# 03_ZIGBEE.net
KiCad netlist of a schematic drawn in Altium Designer
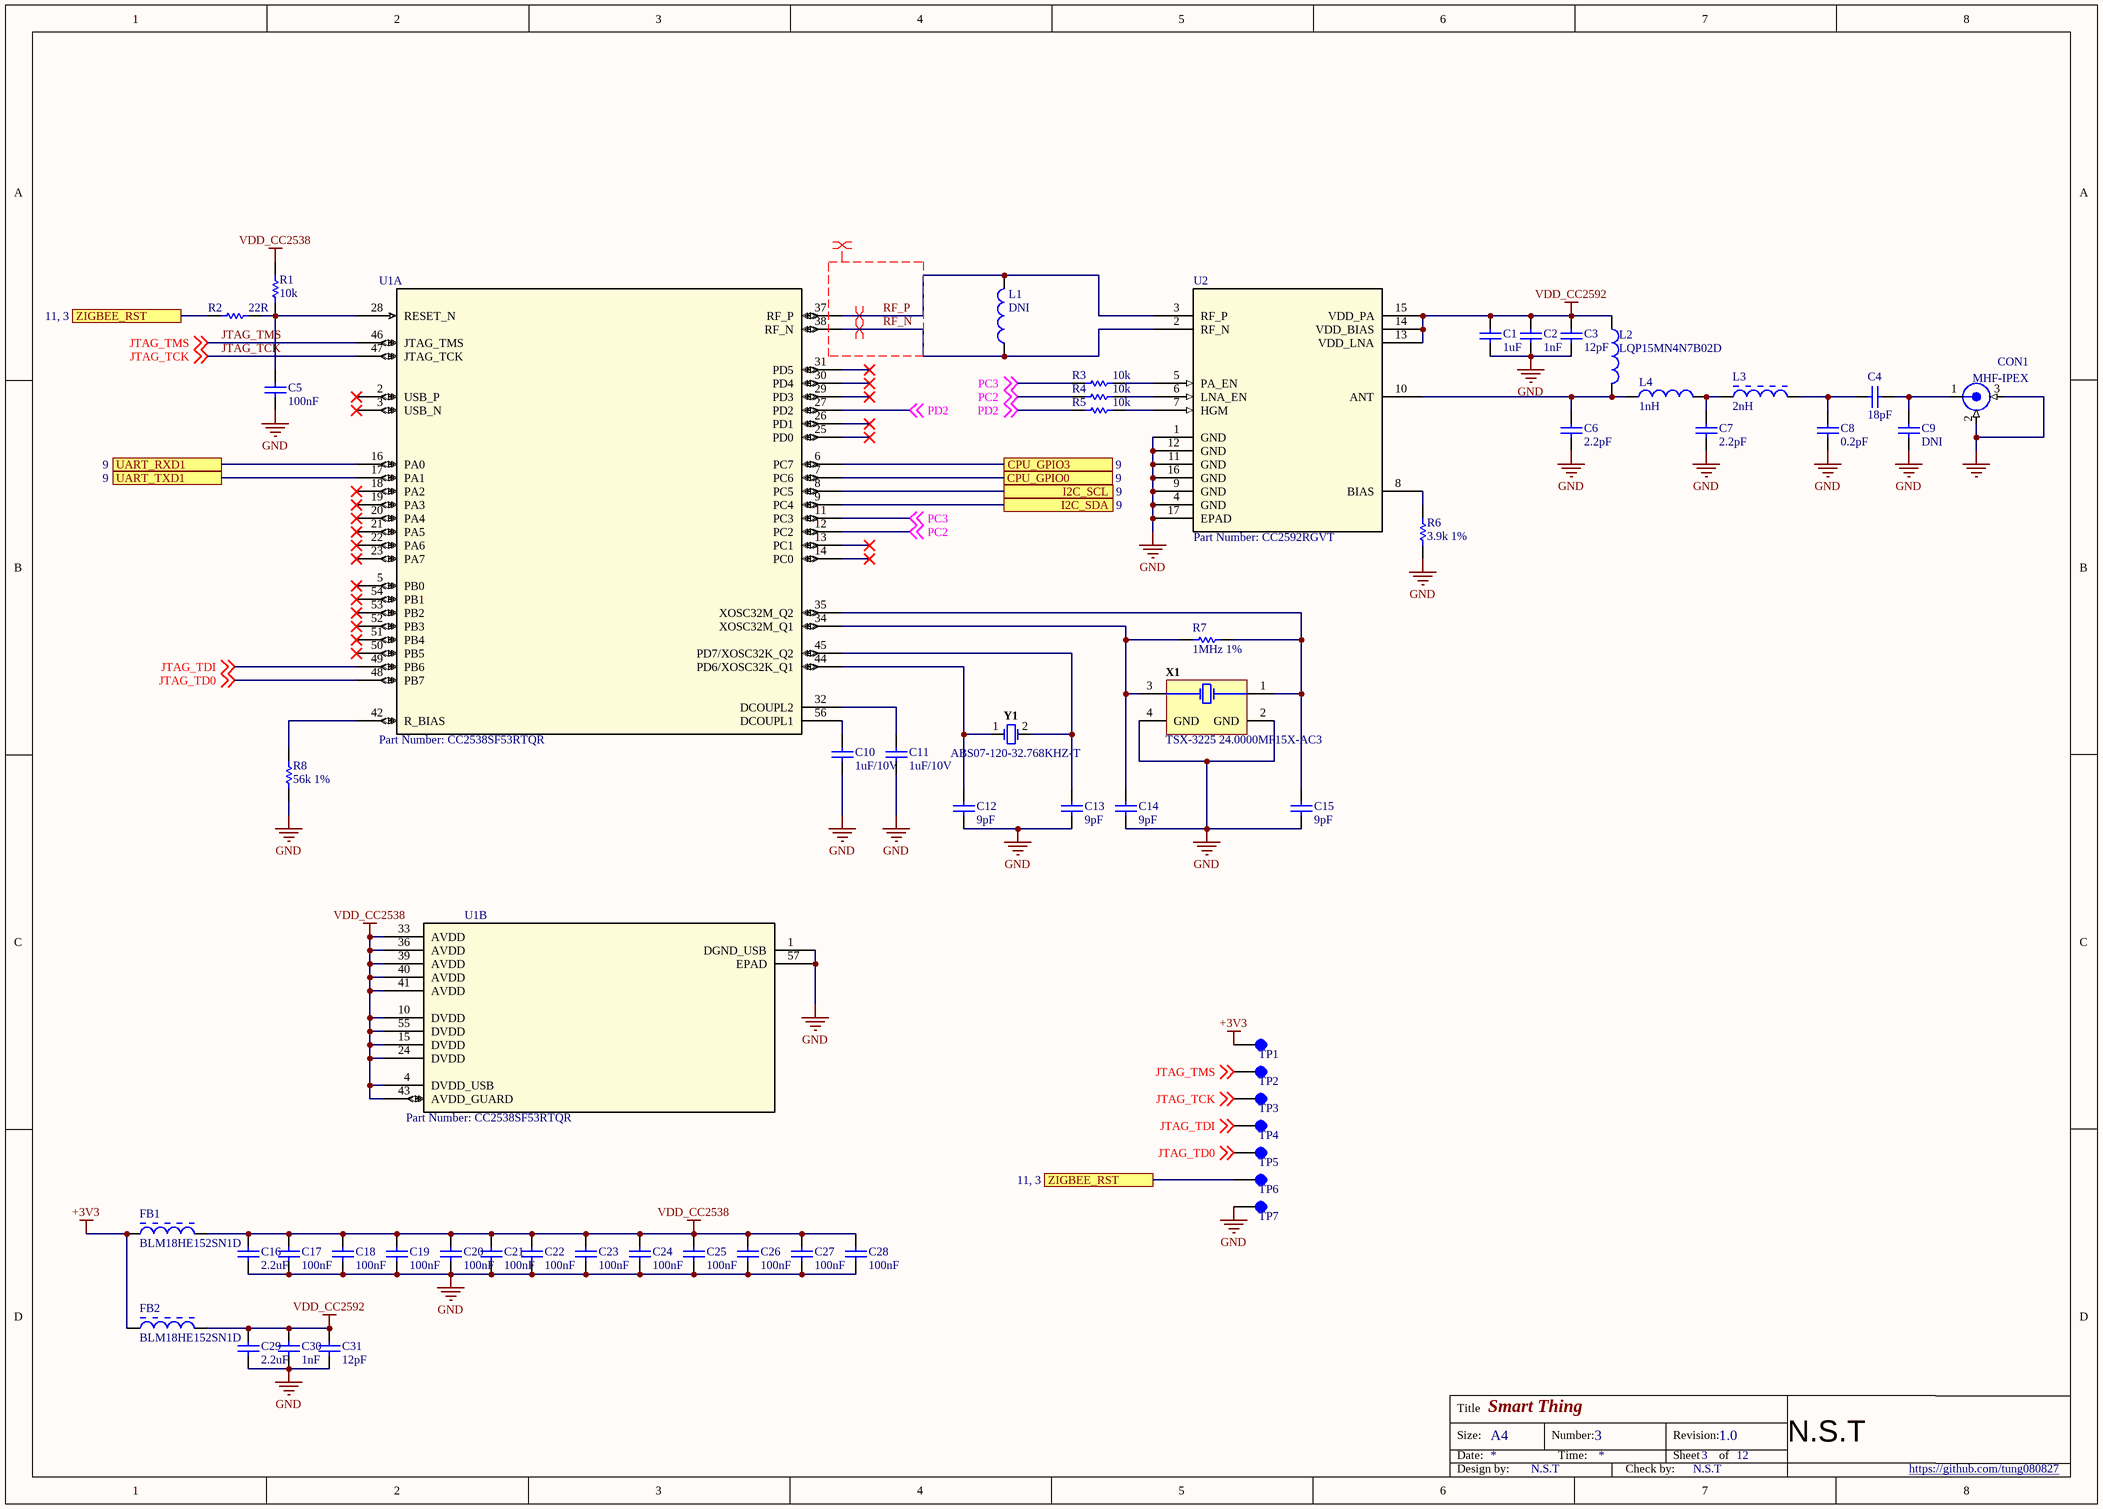
[diagram p0: 03. ZIGBEE.SchDoc]

(export (version "E")
  (design (tool "Eeschema 10.0.6"))
  (components
    (comp (ref "C1")
      (value "1uF")
      (footprint "CAPC1608X90X20NL10")
      (description "Chip Capacitor, 1 uF, +/- 10%, 50 V, -55 to 85 degC, 0603 (1608 Metric), RoHS, Tape and Reel")
      (fields
        (field (name "MANUFACTURER") "TDK")
        (field (name "PCN PART NUMBER") "MLCCPartNumberChange30/Nov/2012")
      )
      (libsource (lib "Altium Content Vault") (part "CAP-NP-2"))
    )
    (comp (ref "C2")
      (value "1nF")
      (footprint "CAPC1005X55X25NL05T10")
      (fields (field (name "PART NUMBER") "GRM1555C1H102JA01D") (field (name "MANUFACTURER") "Murata"))
      (libsource (lib "Altium Content Vault") (part "CAP"))
    )
    (comp (ref "C3")
      (value "12pF")
      (footprint "CAPC1005X55X25NL05T10")
      (fields (field (name "PART NUMBER") "GRM1555C1H120GA01D") (field (name "MANUFACTURER") "Murata"))
      (libsource (lib "Altium Content Vault") (part "CAP"))
    )
    (comp (ref "C4")
      (value "18pF")
      (footprint "CAPC1005X55X25NL05T10")
      (fields (field (name "PART NUMBER") "GJM1555C1H180GB01D") (field (name "MANUFACTURER") "Murata"))
      (libsource (lib "Altium Content Vault") (part "CAP"))
    )
    (comp (ref "C5")
      (value "100nF")
      (footprint "CAPC1005X56X25NL10T15")
      (fields
        (field (name "MANUFACTURER") "AVX Interconnect / Elco")
        (field (name "PART NUMBER") "04026D104KAT2A")
      )
      (libsource (lib "Altium Content Vault") (part "CAP"))
    )
    (comp (ref "C6")
      (value "2.2pF")
      (footprint "CAPC1005X55X25NL05T10")
      (fields (field (name "PART NUMBER") "GJM1555C1H2R2BB01D") (field (name "MANUFACTURER") "Murata"))
      (libsource (lib "Altium Content Vault") (part "CAP"))
    )
    (comp (ref "C7")
      (value "2.2pF")
      (footprint "CAPC1005X55X25NL05T10")
      (fields (field (name "PART NUMBER") "GJM1555C1H2R2BB01D") (field (name "MANUFACTURER") "Murata"))
      (libsource (lib "Altium Content Vault") (part "CAP"))
    )
    (comp (ref "C8")
      (value "0.2pF")
      (footprint "CAPC1005X55X25NL05T10")
      (fields (field (name "PART NUMBER") "GRM1555C1HR20WA01D") (field (name "MANUFACTURER") "Murata"))
      (libsource (lib "Altium Content Vault") (part "CAP"))
    )
    (comp (ref "C9")
      (value "DNI")
      (footprint "CAPC1005X55X25NL05T10")
      (fields (field (name "PART NUMBER") "GJM1555C1H180GB01D") (field (name "MANUFACTURER") "Murata"))
      (libsource (lib "Altium Content Vault") (part "CAP"))
    )
    (comp (ref "C10")
      (value "1uF/10V")
      (footprint "CAPC1005X55X25NL05T10")
      (fields (field (name "PART NUMBER") "GRM155R61A105KE15D") (field (name "MANUFACTURER") "Murata"))
      (libsource (lib "Altium Content Vault") (part "CAP"))
    )
    (comp (ref "C11")
      (value "1uF/10V")
      (footprint "CAPC1005X55X25NL05T10")
      (fields (field (name "PART NUMBER") "GRM155R61A105KE15D") (field (name "MANUFACTURER") "Murata"))
      (libsource (lib "Altium Content Vault") (part "CAP"))
    )
    (comp (ref "C12")
      (value "9pF")
      (footprint "CAPC1005X55X25NL05T10")
      (fields (field (name "PART NUMBER") "GJM1555C1H9R0CB01D") (field (name "MANUFACTURER") "Murata"))
      (libsource (lib "Altium Content Vault") (part "CAP"))
    )
    (comp (ref "C13")
      (value "9pF")
      (footprint "CAPC1005X55X25NL05T10")
      (fields (field (name "PART NUMBER") "GJM1555C1H9R0CB01D") (field (name "MANUFACTURER") "Murata"))
      (libsource (lib "Altium Content Vault") (part "CAP"))
    )
    (comp (ref "C14")
      (value "9pF")
      (footprint "CAPC1005X55X25NL05T10")
      (fields (field (name "PART NUMBER") "GJM1555C1H9R0CB01D") (field (name "MANUFACTURER") "Murata"))
      (libsource (lib "Altium Content Vault") (part "CAP"))
    )
    (comp (ref "C15")
      (value "9pF")
      (footprint "CAPC1005X55X25NL05T10")
      (fields (field (name "PART NUMBER") "GJM1555C1H9R0CB01D") (field (name "MANUFACTURER") "Murata"))
      (libsource (lib "Altium Content Vault") (part "CAP"))
    )
    (comp (ref "C16")
      (value "2.2uF")
      (footprint "CAPC1608X90X35NL10T15")
      (fields (field (name "MANUFACTURER") "Murata") (field (name "PART NUMBER") "GCM188R70J225KE22D"))
      (libsource (lib "Altium Content Vault") (part "CAP"))
    )
    (comp (ref "C17")
      (value "100nF")
      (footprint "CAPC1005X56X25NL10T15")
      (fields
        (field (name "MANUFACTURER") "AVX Interconnect / Elco")
        (field (name "PART NUMBER") "04026D104KAT2A")
      )
      (libsource (lib "Altium Content Vault") (part "CAP"))
    )
    (comp (ref "C18")
      (value "100nF")
      (footprint "CAPC1005X56X25NL10T15")
      (fields
        (field (name "MANUFACTURER") "AVX Interconnect / Elco")
        (field (name "PART NUMBER") "04026D104KAT2A")
      )
      (libsource (lib "Altium Content Vault") (part "CAP"))
    )
    (comp (ref "C19")
      (value "100nF")
      (footprint "CAPC1005X56X25NL10T15")
      (fields
        (field (name "MANUFACTURER") "AVX Interconnect / Elco")
        (field (name "PART NUMBER") "04026D104KAT2A")
      )
      (libsource (lib "Altium Content Vault") (part "CAP"))
    )
    (comp (ref "C20")
      (value "100nF")
      (footprint "CAPC1005X56X25NL10T15")
      (fields
        (field (name "MANUFACTURER") "AVX Interconnect / Elco")
        (field (name "PART NUMBER") "04026D104KAT2A")
      )
      (libsource (lib "Altium Content Vault") (part "CAP"))
    )
    (comp (ref "C21")
      (value "100nF")
      (footprint "CAPC1005X56X25NL10T15")
      (fields
        (field (name "MANUFACTURER") "AVX Interconnect / Elco")
        (field (name "PART NUMBER") "04026D104KAT2A")
      )
      (libsource (lib "Altium Content Vault") (part "CAP"))
    )
    (comp (ref "C22")
      (value "100nF")
      (footprint "CAPC1005X56X25NL10T15")
      (fields
        (field (name "MANUFACTURER") "AVX Interconnect / Elco")
        (field (name "PART NUMBER") "04026D104KAT2A")
      )
      (libsource (lib "Altium Content Vault") (part "CAP"))
    )
    (comp (ref "C23")
      (value "100nF")
      (footprint "CAPC1005X56X25NL10T15")
      (fields
        (field (name "MANUFACTURER") "AVX Interconnect / Elco")
        (field (name "PART NUMBER") "04026D104KAT2A")
      )
      (libsource (lib "Altium Content Vault") (part "CAP"))
    )
    (comp (ref "C24")
      (value "100nF")
      (footprint "CAPC1005X56X25NL10T15")
      (fields
        (field (name "MANUFACTURER") "AVX Interconnect / Elco")
        (field (name "PART NUMBER") "04026D104KAT2A")
      )
      (libsource (lib "Altium Content Vault") (part "CAP"))
    )
    (comp (ref "C25")
      (value "100nF")
      (footprint "CAPC1005X56X25NL10T15")
      (fields
        (field (name "MANUFACTURER") "AVX Interconnect / Elco")
        (field (name "PART NUMBER") "04026D104KAT2A")
      )
      (libsource (lib "Altium Content Vault") (part "CAP"))
    )
    (comp (ref "C26")
      (value "100nF")
      (footprint "CAPC1005X56X25NL10T15")
      (fields
        (field (name "MANUFACTURER") "AVX Interconnect / Elco")
        (field (name "PART NUMBER") "04026D104KAT2A")
      )
      (libsource (lib "Altium Content Vault") (part "CAP"))
    )
    (comp (ref "C27")
      (value "100nF")
      (footprint "CAPC1005X56X25NL10T15")
      (fields
        (field (name "MANUFACTURER") "AVX Interconnect / Elco")
        (field (name "PART NUMBER") "04026D104KAT2A")
      )
      (libsource (lib "Altium Content Vault") (part "CAP"))
    )
    (comp (ref "C28")
      (value "100nF")
      (footprint "CAPC1005X56X25NL10T15")
      (fields
        (field (name "MANUFACTURER") "AVX Interconnect / Elco")
        (field (name "PART NUMBER") "04026D104KAT2A")
      )
      (libsource (lib "Altium Content Vault") (part "CAP"))
    )
    (comp (ref "C29")
      (value "2.2uF")
      (footprint "CAPC1608X90X35NL10T15")
      (fields (field (name "MANUFACTURER") "Murata") (field (name "PART NUMBER") "GCM188R70J225KE22D"))
      (libsource (lib "Altium Content Vault") (part "CAP"))
    )
    (comp (ref "C30")
      (value "1nF")
      (footprint "CAPC1005X55X25NL05T10")
      (fields (field (name "PART NUMBER") "GRM1555C1H102JA01D") (field (name "MANUFACTURER") "Murata"))
      (libsource (lib "Altium Content Vault") (part "CAP"))
    )
    (comp (ref "C31")
      (value "12pF")
      (footprint "CAPC1005X55X25NL05T10")
      (fields (field (name "PART NUMBER") "GRM1555C1H120GA01D") (field (name "MANUFACTURER") "Murata"))
      (libsource (lib "Altium Content Vault") (part "CAP"))
    )
    (comp (ref "CON1")
      (value "MHF-IPEX")
      (footprint "I-PEX CON")
      (libsource (lib "MT7688AN") (part "SMA/UFLR"))
    )
    (comp (ref "FB1")
      (value "BLM18HE152SN1D")
      (footprint "MURA-BLM18-RF-H4-CHIP-2_V")
      (fields (field (name "MANUFACTURER") "Murata"))
      (libsource (lib "Altium Content Vault") (part "MURA-FB-2"))
    )
    (comp (ref "FB2")
      (value "BLM18HE152SN1D")
      (footprint "MURA-BLM18-RF-H4-CHIP-2_V")
      (fields (field (name "MANUFACTURER") "Murata"))
      (libsource (lib "Altium Content Vault") (part "MURA-FB-2"))
    )
    (comp (ref "L1")
      (value "DNI")
      (footprint "INDC1005X45X25NL10T10")
      (description "Chip Inductor, 1.8 nH, +/- 0.1 nH, 280 mA, -40 to 85 degC, 0402 (1005 Metric), RoHS, Tape and Reel")
      (fields (field (name "MANUFACTURER") "Murata"))
      (libsource (lib "Altium Content Vault") (part "IND-2"))
    )
    (comp (ref "L2")
      (value "LQP15MN4N7B02D")
      (footprint "INDC1005X45X25LL10T10")
      (description "Chip Inductor, 4.7 nH, +/- 0.1 nH, 160 mA, -40 to 85 degC, 0402 (1005 Metric), RoHS, Tape and Reel")
      (fields (field (name "MANUFACTURER") "Murata") (field (name "TOLERANCE") "0.1nH"))
      (libsource (lib "Altium Content Vault") (part "IND-2"))
    )
    (comp (ref "L3")
      (value "2nH")
      (footprint "MURA-IND0402_V")
      (fields (field (name "MANUFACTURER") "Murata") (field (name "PARTNUMBER") "LQG15HS2N0S02D"))
      (libsource (lib "Altium Content Vault") (part "MURA-INDC-2"))
    )
    (comp (ref "L4")
      (value "1nH")
      (footprint "INDC1005X45X25NL10T10")
      (description "Chip Inductor, 1 nH, +/- 0.1 nH, 400 mA, -40 to 85 degC, 0402 (1005 Metric), RoHS, Tape and Reel")
      (fields (field (name "PARTNUMBER") "LQP15MN1N0B02D"))
      (libsource (lib "Altium Content Vault") (part "IND-2"))
    )
    (comp (ref "R1")
      (value "10k")
      (footprint "RESC1005X40X25NL05T05")
      (fields (field (name "MANUFACTURER") "Vishay Dale") (field (name "PART NUMBER") "CRCW040210K0FKED"))
      (libsource (lib "Altium Content Vault") (part "RES"))
    )
    (comp (ref "R2")
      (value "22R")
      (footprint "RESC1005X40X25LL05T05")
      (description "Chip Resistor, 22 Ohm, +/- 1%, 0.1 W, -55 to 155 degC, 0402 (1005 Metric), RoHS, Tape and Reel")
      (fields (field (name "PARTNUMBER") "ERJ-2RKF22R0X") (field (name "TOLERANCE") "1%"))
      (libsource (lib "AM3358_DEV_BOARD") (part "RES-2"))
    )
    (comp (ref "R3")
      (value "10k")
      (footprint "RESC1005X40X25NL05T05")
      (fields (field (name "MANUFACTURER") "Vishay Dale") (field (name "PART NUMBER") "CRCW040210K0FKED"))
      (libsource (lib "Altium Content Vault") (part "RES"))
    )
    (comp (ref "R4")
      (value "10k")
      (footprint "RESC1005X40X25NL05T05")
      (fields (field (name "MANUFACTURER") "Vishay Dale") (field (name "PART NUMBER") "CRCW040210K0FKED"))
      (libsource (lib "Altium Content Vault") (part "RES"))
    )
    (comp (ref "R5")
      (value "10k")
      (footprint "RESC1005X40X25NL05T05")
      (fields (field (name "MANUFACTURER") "Vishay Dale") (field (name "PART NUMBER") "CRCW040210K0FKED"))
      (libsource (lib "Altium Content Vault") (part "RES"))
    )
    (comp (ref "R6")
      (value "3.9k 1%")
      (footprint "RESC1005X40X25NL05T05")
      (fields (field (name "MANUFACTURER") "Vishay Dale") (field (name "PART NUMBER") "CRCW04023K90FKED"))
      (libsource (lib "Altium Content Vault") (part "RES"))
    )
    (comp (ref "R7")
      (value "1MHz 1%")
      (footprint "RESC1005X40X25NL05T05")
      (fields (field (name "PART NUMBER") "CRCW04020000Z0ED") (field (name "MANUFACTURER") "Vishay Dale"))
      (libsource (lib "Altium Content Vault") (part "RES"))
    )
    (comp (ref "R8")
      (value "56k 1%")
      (footprint "RESC1005X40X25NL05T05")
      (fields (field (name "PART NUMBER") "CRCW040256K0FKED") (field (name "MANUFACTURER") "Vishay Dale"))
      (libsource (lib "Altium Content Vault") (part "RES"))
    )
    (comp (ref "TP1") (value "Test Point") (footprint "TP") (libsource (lib "SyTungNguyen") (part "TP")))
    (comp (ref "TP2") (value "Test Point") (footprint "TP") (libsource (lib "SyTungNguyen") (part "TP")))
    (comp (ref "TP3") (value "Test Point") (footprint "TP") (libsource (lib "SyTungNguyen") (part "TP")))
    (comp (ref "TP4") (value "Test Point") (footprint "TP") (libsource (lib "SyTungNguyen") (part "TP")))
    (comp (ref "TP5") (value "Test Point") (footprint "TP") (libsource (lib "SyTungNguyen") (part "TP")))
    (comp (ref "TP6") (value "Test Point") (footprint "TP") (libsource (lib "SyTungNguyen") (part "TP")))
    (comp (ref "TP7") (value "Test Point") (footprint "TP") (libsource (lib "SyTungNguyen") (part "TP")))
    (comp (ref "U1")
      (value "Part Number: CC2538SF53RTQR")
      (footprint "QFN56_6P7X6P7")
      (description "IC RF TxRx + MCU 802.15.4 6LoWPAN, Zigbee® 2.4GHz 56-VFQFN Exposed Pad")
      (fields
        (field (name "MANUFACTURER_PART_NUMBER") "CC2538SF53RTQR")
        (field (name "COPYRIGHT") "Copyright (C) 2018 Accelerated Designs. All rights reserved")
      )
      (libsource (lib "SyTungNguyen") (part "CC2538SF53RTQR"))
    )
    (comp (ref "U2")
      (value "Part Number: CC2592RGVT")
      (footprint "QFN16_2P16X2P16")
      (description "No Description Available")
      (fields
        (field (name "MANUFACTURER_PART_NUMBER") "CC2592RGVT")
        (field (name "COPYRIGHT") "Copyright (C) 2018 Accelerated Designs. All rights reserved")
      )
      (libsource (lib "SyTungNguyen") (part "CC2592RGVT"))
    )
    (comp (ref "X1")
      (value "TSX-3225 24.0000MF15X-AC3")
      (footprint "FP-NX3225SA-MFG")
      (description "MHz Range Crystal, 24 MHz, -40 to 85 degC, 4-Pin SMD, RoHS, Tape and Reel")
      (fields (field (name "TOLERANCE") "10PPM") (field (name "MANUFACTURER") "Epson"))
      (libsource (lib "AM3358_DEV_BOARD") (part "XTAL-1-3-4"))
    )
    (comp (ref "Y1")
      (value "ABS07-120-32.768KHZ-T")
      (footprint "ABRA-ABS07_A_V")
      (description "Tuning Fork Crystal, 32.768 KHz, +/- 20 ppm, -40 to 85 degC, 2-Pin SMD, RoHS, Tape and Reel")
      (fields (field (name "MANUFACTURER") "Abracon") (field (name "TOLERANCE") "20ppm"))
      (libsource (lib "Altium Content Vault") (part "XTAL-1-2-2"))
    )
  )
  (nets
    (net (code "1") (name "+3V3") (class "Default")
      (node (ref "FB1") (pin "1") (pinfunction "1_1") (pintype "passive"))
      (node (ref "FB2") (pin "1") (pinfunction "1_1") (pintype "passive"))
      (node (ref "TP1") (pin "1") (pintype "passive"))
    )
    (net (code "2") (name "/CPU_GPIO0") (class "Default")
      (node (ref "U1") (pin "7") (pinfunction "PC6_7") (pintype "bidirectional"))
    )
    (net (code "3") (name "/CPU_GPIO3") (class "Default")
      (node (ref "U1") (pin "6") (pinfunction "PC7_6") (pintype "bidirectional"))
    )
    (net (code "4") (name "/I2C_SCL") (class "Default")
      (node (ref "U1") (pin "8") (pinfunction "PC5_8") (pintype "bidirectional"))
    )
    (net (code "5") (name "/I2C_SDA") (class "Default")
      (node (ref "U1") (pin "9") (pinfunction "PC4_9") (pintype "bidirectional"))
    )
    (net (code "6") (name "/RF_N") (class "Default")
      (node (ref "L1") (pin "1") (pinfunction "1_1") (pintype "passive"))
      (node (ref "U1") (pin "38") (pinfunction "RF_N_38") (pintype "bidirectional"))
      (node (ref "U2") (pin "2") (pinfunction "RF_N_2") (pintype "passive"))
    )
    (net (code "7") (name "/RF_P") (class "Default")
      (node (ref "L1") (pin "2") (pinfunction "2_2") (pintype "passive"))
      (node (ref "U1") (pin "37") (pinfunction "RF_P_37") (pintype "bidirectional"))
      (node (ref "U2") (pin "3") (pinfunction "RF_P_3") (pintype "passive"))
    )
    (net (code "8") (name "/UART_RXD1") (class "Default")
      (node (ref "U1") (pin "16") (pinfunction "PA0_16") (pintype "bidirectional"))
    )
    (net (code "9") (name "/UART_TXD1") (class "Default")
      (node (ref "U1") (pin "17") (pinfunction "PA1_17") (pintype "bidirectional"))
    )
    (net (code "10") (name "/ZIGBEE_RST") (class "Default")
      (node (ref "R2") (pin "1") (pinfunction "1_1") (pintype "passive"))
      (node (ref "TP6") (pin "1") (pintype "passive"))
    )
    (net (code "11") (name "GND") (class "Default")
      (node (ref "C1") (pin "1") (pinfunction "1_1") (pintype "passive"))
      (node (ref "C10") (pin "1") (pinfunction "1_1") (pintype "passive"))
      (node (ref "C11") (pin "1") (pinfunction "1_1") (pintype "passive"))
      (node (ref "C12") (pin "1") (pinfunction "1_1") (pintype "passive"))
      (node (ref "C13") (pin "1") (pinfunction "1_1") (pintype "passive"))
      (node (ref "C14") (pin "1") (pinfunction "1_1") (pintype "passive"))
      (node (ref "C15") (pin "1") (pinfunction "1_1") (pintype "passive"))
      (node (ref "C16") (pin "1") (pinfunction "1_1") (pintype "passive"))
      (node (ref "C17") (pin "1") (pinfunction "1_1") (pintype "passive"))
      (node (ref "C18") (pin "1") (pinfunction "1_1") (pintype "passive"))
      (node (ref "C19") (pin "1") (pinfunction "1_1") (pintype "passive"))
      (node (ref "C2") (pin "1") (pinfunction "1_1") (pintype "passive"))
      (node (ref "C20") (pin "1") (pinfunction "1_1") (pintype "passive"))
      (node (ref "C21") (pin "1") (pinfunction "1_1") (pintype "passive"))
      (node (ref "C22") (pin "1") (pinfunction "1_1") (pintype "passive"))
      (node (ref "C23") (pin "1") (pinfunction "1_1") (pintype "passive"))
      (node (ref "C24") (pin "1") (pinfunction "1_1") (pintype "passive"))
      (node (ref "C25") (pin "1") (pinfunction "1_1") (pintype "passive"))
      (node (ref "C26") (pin "1") (pinfunction "1_1") (pintype "passive"))
      (node (ref "C27") (pin "1") (pinfunction "1_1") (pintype "passive"))
      (node (ref "C28") (pin "1") (pinfunction "1_1") (pintype "passive"))
      (node (ref "C29") (pin "1") (pinfunction "1_1") (pintype "passive"))
      (node (ref "C3") (pin "1") (pinfunction "1_1") (pintype "passive"))
      (node (ref "C30") (pin "1") (pinfunction "1_1") (pintype "passive"))
      (node (ref "C31") (pin "1") (pinfunction "1_1") (pintype "passive"))
      (node (ref "C5") (pin "1") (pinfunction "1_1") (pintype "passive"))
      (node (ref "C6") (pin "1") (pinfunction "1_1") (pintype "passive"))
      (node (ref "C7") (pin "1") (pinfunction "1_1") (pintype "passive"))
      (node (ref "C8") (pin "1") (pinfunction "1_1") (pintype "passive"))
      (node (ref "C9") (pin "1") (pinfunction "1_1") (pintype "passive"))
      (node (ref "CON1") (pin "2") (pinfunction "2_2") (pintype "input"))
      (node (ref "CON1") (pin "3") (pinfunction "GNDA_3") (pintype "input"))
      (node (ref "R6") (pin "1") (pinfunction "1_1") (pintype "passive"))
      (node (ref "R8") (pin "1") (pinfunction "1_1") (pintype "passive"))
      (node (ref "TP7") (pin "1") (pintype "passive"))
      (node (ref "U1") (pin "1") (pinfunction "DGND_USB_1") (pintype "power_in"))
      (node (ref "U1") (pin "57") (pinfunction "EPAD_57") (pintype "passive"))
      (node (ref "U2") (pin "1") (pinfunction "GND_1") (pintype "power_in"))
      (node (ref "U2") (pin "11") (pinfunction "GND_11") (pintype "power_in"))
      (node (ref "U2") (pin "12") (pinfunction "GND_12") (pintype "power_in"))
      (node (ref "U2") (pin "16") (pinfunction "GND_16") (pintype "power_in"))
      (node (ref "U2") (pin "17") (pinfunction "EPAD_17") (pintype "passive"))
      (node (ref "U2") (pin "4") (pinfunction "GND_4") (pintype "power_in"))
      (node (ref "U2") (pin "9") (pinfunction "GND_9") (pintype "power_in"))
      (node (ref "X1") (pin "2") (pinfunction "GND_2") (pintype "power_in"))
      (node (ref "X1") (pin "4") (pinfunction "GND_4") (pintype "power_in"))
    )
    (net (code "12") (name "JTAG_TCK") (class "Default")
      (node (ref "TP3") (pin "1") (pintype "passive"))
      (node (ref "U1") (pin "47") (pinfunction "JTAG_TCK_47") (pintype "bidirectional"))
    )
    (net (code "13") (name "JTAG_TD0") (class "Default")
      (node (ref "TP5") (pin "1") (pintype "passive"))
      (node (ref "U1") (pin "48") (pinfunction "PB7_48") (pintype "bidirectional"))
    )
    (net (code "14") (name "JTAG_TDI") (class "Default")
      (node (ref "TP4") (pin "1") (pintype "passive"))
      (node (ref "U1") (pin "49") (pinfunction "PB6_49") (pintype "bidirectional"))
    )
    (net (code "15") (name "JTAG_TMS") (class "Default")
      (node (ref "TP2") (pin "1") (pintype "passive"))
      (node (ref "U1") (pin "46") (pinfunction "JTAG_TMS_46") (pintype "bidirectional"))
    )
    (net (code "16") (name "Net-(C4-Pad1)") (class "Default")
      (node (ref "C4") (pin "1") (pinfunction "1_1") (pintype "passive"))
      (node (ref "C8") (pin "2") (pinfunction "2_2") (pintype "passive"))
      (node (ref "L3") (pin "2") (pinfunction "2_2") (pintype "passive"))
    )
    (net (code "17") (name "Net-(C4-Pad2)") (class "Default")
      (node (ref "C4") (pin "2") (pinfunction "2_2") (pintype "passive"))
      (node (ref "C9") (pin "2") (pinfunction "2_2") (pintype "passive"))
      (node (ref "CON1") (pin "1") (pinfunction "1_1") (pintype "passive"))
    )
    (net (code "18") (name "Net-(C7-Pad2)") (class "Default")
      (node (ref "C7") (pin "2") (pinfunction "2_2") (pintype "passive"))
      (node (ref "L3") (pin "1") (pinfunction "1_1") (pintype "passive"))
      (node (ref "L4") (pin "2") (pinfunction "2_2") (pintype "passive"))
    )
    (net (code "19") (name "Net-(U1A-DCOUPL1)") (class "Default")
      (node (ref "C10") (pin "2") (pinfunction "2_2") (pintype "passive"))
      (node (ref "U1") (pin "56") (pinfunction "DCOUPL1_56") (pintype "power_in"))
    )
    (net (code "20") (name "Net-(U1A-DCOUPL2)") (class "Default")
      (node (ref "C11") (pin "2") (pinfunction "2_2") (pintype "passive"))
      (node (ref "U1") (pin "32") (pinfunction "DCOUPL2_32") (pintype "power_in"))
    )
    (net (code "21") (name "Net-(U1A-PD6{slash}XOSC32K_Q1)") (class "Default")
      (node (ref "C12") (pin "2") (pinfunction "2_2") (pintype "passive"))
      (node (ref "U1") (pin "44") (pinfunction "PD6/XOSC32K_Q1_44") (pintype "bidirectional"))
      (node (ref "Y1") (pin "1") (pinfunction "1_1") (pintype "passive"))
    )
    (net (code "22") (name "Net-(U1A-PD7{slash}XOSC32K_Q2)") (class "Default")
      (node (ref "C13") (pin "2") (pinfunction "2_2") (pintype "passive"))
      (node (ref "U1") (pin "45") (pinfunction "PD7/XOSC32K_Q2_45") (pintype "bidirectional"))
      (node (ref "Y1") (pin "2") (pinfunction "2_2") (pintype "passive"))
    )
    (net (code "23") (name "Net-(U1A-RESET_N)") (class "Default")
      (node (ref "C5") (pin "2") (pinfunction "2_2") (pintype "passive"))
      (node (ref "R1") (pin "1") (pinfunction "1_1") (pintype "passive"))
      (node (ref "R2") (pin "2") (pinfunction "2_2") (pintype "passive"))
      (node (ref "U1") (pin "28") (pinfunction "RESET_N_28") (pintype "input"))
    )
    (net (code "24") (name "Net-(U1A-R_BIAS)") (class "Default")
      (node (ref "R8") (pin "2") (pinfunction "2_2") (pintype "passive"))
      (node (ref "U1") (pin "42") (pinfunction "R_BIAS_42") (pintype "bidirectional"))
    )
    (net (code "25") (name "Net-(U1A-XOSC32M_Q1)") (class "Default")
      (node (ref "C14") (pin "2") (pinfunction "2_2") (pintype "passive"))
      (node (ref "R7") (pin "1") (pinfunction "1_1") (pintype "passive"))
      (node (ref "U1") (pin "34") (pinfunction "XOSC32M_Q1_34") (pintype "bidirectional"))
      (node (ref "X1") (pin "3") (pinfunction "X2_3") (pintype "passive"))
    )
    (net (code "26") (name "Net-(U1A-XOSC32M_Q2)") (class "Default")
      (node (ref "C15") (pin "2") (pinfunction "2_2") (pintype "passive"))
      (node (ref "R7") (pin "2") (pinfunction "2_2") (pintype "passive"))
      (node (ref "U1") (pin "35") (pinfunction "XOSC32M_Q2_35") (pintype "bidirectional"))
      (node (ref "X1") (pin "1") (pinfunction "X1_1") (pintype "passive"))
    )
    (net (code "27") (name "Net-(U2-ANT)") (class "Default")
      (node (ref "C6") (pin "2") (pinfunction "2_2") (pintype "passive"))
      (node (ref "L2") (pin "2") (pinfunction "2_2") (pintype "passive"))
      (node (ref "L4") (pin "1") (pinfunction "1_1") (pintype "passive"))
      (node (ref "U2") (pin "10") (pinfunction "ANT_10") (pintype "passive"))
    )
    (net (code "28") (name "Net-(U2-BIAS)") (class "Default")
      (node (ref "R6") (pin "2") (pinfunction "2_2") (pintype "passive"))
      (node (ref "U2") (pin "8") (pinfunction "BIAS_8") (pintype "passive"))
    )
    (net (code "29") (name "Net-(U2-HGM)") (class "Default")
      (node (ref "R5") (pin "2") (pinfunction "2_2") (pintype "passive"))
      (node (ref "U2") (pin "7") (pinfunction "HGM_7") (pintype "input"))
    )
    (net (code "30") (name "Net-(U2-LNA_EN)") (class "Default")
      (node (ref "R4") (pin "2") (pinfunction "2_2") (pintype "passive"))
      (node (ref "U2") (pin "6") (pinfunction "LNA_EN_6") (pintype "input"))
    )
    (net (code "31") (name "Net-(U2-PA_EN)") (class "Default")
      (node (ref "R3") (pin "2") (pinfunction "2_2") (pintype "passive"))
      (node (ref "U2") (pin "5") (pinfunction "PA_EN_5") (pintype "input"))
    )
    (net (code "32") (name "PC2") (class "Default")
      (node (ref "R4") (pin "1") (pinfunction "1_1") (pintype "passive"))
      (node (ref "U1") (pin "12") (pinfunction "PC2_12") (pintype "bidirectional"))
    )
    (net (code "33") (name "PC3") (class "Default")
      (node (ref "R3") (pin "1") (pinfunction "1_1") (pintype "passive"))
      (node (ref "U1") (pin "11") (pinfunction "PC3_11") (pintype "bidirectional"))
    )
    (net (code "34") (name "PD2") (class "Default")
      (node (ref "R5") (pin "1") (pinfunction "1_1") (pintype "passive"))
      (node (ref "U1") (pin "27") (pinfunction "PD2_27") (pintype "bidirectional"))
    )
    (net (code "35") (name "VDD_CC2538") (class "Default")
      (node (ref "C16") (pin "2") (pinfunction "2_2") (pintype "passive"))
      (node (ref "C17") (pin "2") (pinfunction "2_2") (pintype "passive"))
      (node (ref "C18") (pin "2") (pinfunction "2_2") (pintype "passive"))
      (node (ref "C19") (pin "2") (pinfunction "2_2") (pintype "passive"))
      (node (ref "C20") (pin "2") (pinfunction "2_2") (pintype "passive"))
      (node (ref "C21") (pin "2") (pinfunction "2_2") (pintype "passive"))
      (node (ref "C22") (pin "2") (pinfunction "2_2") (pintype "passive"))
      (node (ref "C23") (pin "2") (pinfunction "2_2") (pintype "passive"))
      (node (ref "C24") (pin "2") (pinfunction "2_2") (pintype "passive"))
      (node (ref "C25") (pin "2") (pinfunction "2_2") (pintype "passive"))
      (node (ref "C26") (pin "2") (pinfunction "2_2") (pintype "passive"))
      (node (ref "C27") (pin "2") (pinfunction "2_2") (pintype "passive"))
      (node (ref "C28") (pin "2") (pinfunction "2_2") (pintype "passive"))
      (node (ref "FB1") (pin "2") (pinfunction "2_2") (pintype "passive"))
      (node (ref "R1") (pin "2") (pinfunction "2_2") (pintype "passive"))
      (node (ref "U1") (pin "10") (pinfunction "DVDD_10") (pintype "power_in"))
      (node (ref "U1") (pin "15") (pinfunction "DVDD_15") (pintype "power_in"))
      (node (ref "U1") (pin "24") (pinfunction "DVDD_24") (pintype "power_in"))
      (node (ref "U1") (pin "33") (pinfunction "AVDD_33") (pintype "power_in"))
      (node (ref "U1") (pin "36") (pinfunction "AVDD_36") (pintype "power_in"))
      (node (ref "U1") (pin "39") (pinfunction "AVDD_39") (pintype "power_in"))
      (node (ref "U1") (pin "4") (pinfunction "DVDD_USB_4") (pintype "power_in"))
      (node (ref "U1") (pin "40") (pinfunction "AVDD_40") (pintype "power_in"))
      (node (ref "U1") (pin "41") (pinfunction "AVDD_41") (pintype "power_in"))
      (node (ref "U1") (pin "43") (pinfunction "AVDD_GUARD_43") (pintype "bidirectional"))
      (node (ref "U1") (pin "55") (pinfunction "DVDD_55") (pintype "power_in"))
    )
    (net (code "36") (name "VDD_CC2592") (class "Default")
      (node (ref "C1") (pin "2") (pinfunction "2_2") (pintype "passive"))
      (node (ref "C2") (pin "2") (pinfunction "2_2") (pintype "passive"))
      (node (ref "C29") (pin "2") (pinfunction "2_2") (pintype "passive"))
      (node (ref "C3") (pin "2") (pinfunction "2_2") (pintype "passive"))
      (node (ref "C30") (pin "2") (pinfunction "2_2") (pintype "passive"))
      (node (ref "C31") (pin "2") (pinfunction "2_2") (pintype "passive"))
      (node (ref "FB2") (pin "2") (pinfunction "2_2") (pintype "passive"))
      (node (ref "L2") (pin "1") (pinfunction "1_1") (pintype "passive"))
      (node (ref "U2") (pin "13") (pinfunction "VDD_LNA_13") (pintype "power_in"))
      (node (ref "U2") (pin "14") (pinfunction "VDD_BIAS_14") (pintype "power_in"))
      (node (ref "U2") (pin "15") (pinfunction "VDD_PA_15") (pintype "power_in"))
    )
    (net (code "37") (name "unconnected-(U1A-PA2-Pad18)") (class "Default")
      (node (ref "U1") (pin "18") (pinfunction "PA2_18") (pintype "bidirectional+no_connect"))
    )
    (net (code "38") (name "unconnected-(U1A-PA3-Pad19)") (class "Default")
      (node (ref "U1") (pin "19") (pinfunction "PA3_19") (pintype "bidirectional+no_connect"))
    )
    (net (code "39") (name "unconnected-(U1A-PA4-Pad20)") (class "Default")
      (node (ref "U1") (pin "20") (pinfunction "PA4_20") (pintype "bidirectional+no_connect"))
    )
    (net (code "40") (name "unconnected-(U1A-PA5-Pad21)") (class "Default")
      (node (ref "U1") (pin "21") (pinfunction "PA5_21") (pintype "bidirectional+no_connect"))
    )
    (net (code "41") (name "unconnected-(U1A-PA6-Pad22)") (class "Default")
      (node (ref "U1") (pin "22") (pinfunction "PA6_22") (pintype "bidirectional+no_connect"))
    )
    (net (code "42") (name "unconnected-(U1A-PA7-Pad23)") (class "Default")
      (node (ref "U1") (pin "23") (pinfunction "PA7_23") (pintype "bidirectional+no_connect"))
    )
    (net (code "43") (name "unconnected-(U1A-PB0-Pad5)") (class "Default")
      (node (ref "U1") (pin "5") (pinfunction "PB0_5") (pintype "bidirectional+no_connect"))
    )
    (net (code "44") (name "unconnected-(U1A-PB1-Pad54)") (class "Default")
      (node (ref "U1") (pin "54") (pinfunction "PB1_54") (pintype "bidirectional+no_connect"))
    )
    (net (code "45") (name "unconnected-(U1A-PB2-Pad53)") (class "Default")
      (node (ref "U1") (pin "53") (pinfunction "PB2_53") (pintype "bidirectional+no_connect"))
    )
    (net (code "46") (name "unconnected-(U1A-PB3-Pad52)") (class "Default")
      (node (ref "U1") (pin "52") (pinfunction "PB3_52") (pintype "bidirectional+no_connect"))
    )
    (net (code "47") (name "unconnected-(U1A-PB4-Pad51)") (class "Default")
      (node (ref "U1") (pin "51") (pinfunction "PB4_51") (pintype "bidirectional+no_connect"))
    )
    (net (code "48") (name "unconnected-(U1A-PB5-Pad50)") (class "Default")
      (node (ref "U1") (pin "50") (pinfunction "PB5_50") (pintype "bidirectional+no_connect"))
    )
    (net (code "49") (name "unconnected-(U1A-PC0-Pad14)") (class "Default")
      (node (ref "U1") (pin "14") (pinfunction "PC0_14") (pintype "bidirectional+no_connect"))
    )
    (net (code "50") (name "unconnected-(U1A-PC1-Pad13)") (class "Default")
      (node (ref "U1") (pin "13") (pinfunction "PC1_13") (pintype "bidirectional+no_connect"))
    )
    (net (code "51") (name "unconnected-(U1A-PD0-Pad25)") (class "Default")
      (node (ref "U1") (pin "25") (pinfunction "PD0_25") (pintype "bidirectional+no_connect"))
    )
    (net (code "52") (name "unconnected-(U1A-PD1-Pad26)") (class "Default")
      (node (ref "U1") (pin "26") (pinfunction "PD1_26") (pintype "bidirectional+no_connect"))
    )
    (net (code "53") (name "unconnected-(U1A-PD3-Pad29)") (class "Default")
      (node (ref "U1") (pin "29") (pinfunction "PD3_29") (pintype "bidirectional+no_connect"))
    )
    (net (code "54") (name "unconnected-(U1A-PD4-Pad30)") (class "Default")
      (node (ref "U1") (pin "30") (pinfunction "PD4_30") (pintype "bidirectional+no_connect"))
    )
    (net (code "55") (name "unconnected-(U1A-PD5-Pad31)") (class "Default")
      (node (ref "U1") (pin "31") (pinfunction "PD5_31") (pintype "bidirectional+no_connect"))
    )
    (net (code "56") (name "unconnected-(U1A-USB_N-Pad3)") (class "Default")
      (node (ref "U1") (pin "3") (pinfunction "USB_N_3") (pintype "bidirectional+no_connect"))
    )
    (net (code "57") (name "unconnected-(U1A-USB_P-Pad2)") (class "Default")
      (node (ref "U1") (pin "2") (pinfunction "USB_P_2") (pintype "bidirectional+no_connect"))
    )
  )
)
